# STM32_Minimum_System.net
KiCad netlist of a schematic drawn in EasyEDA Pro
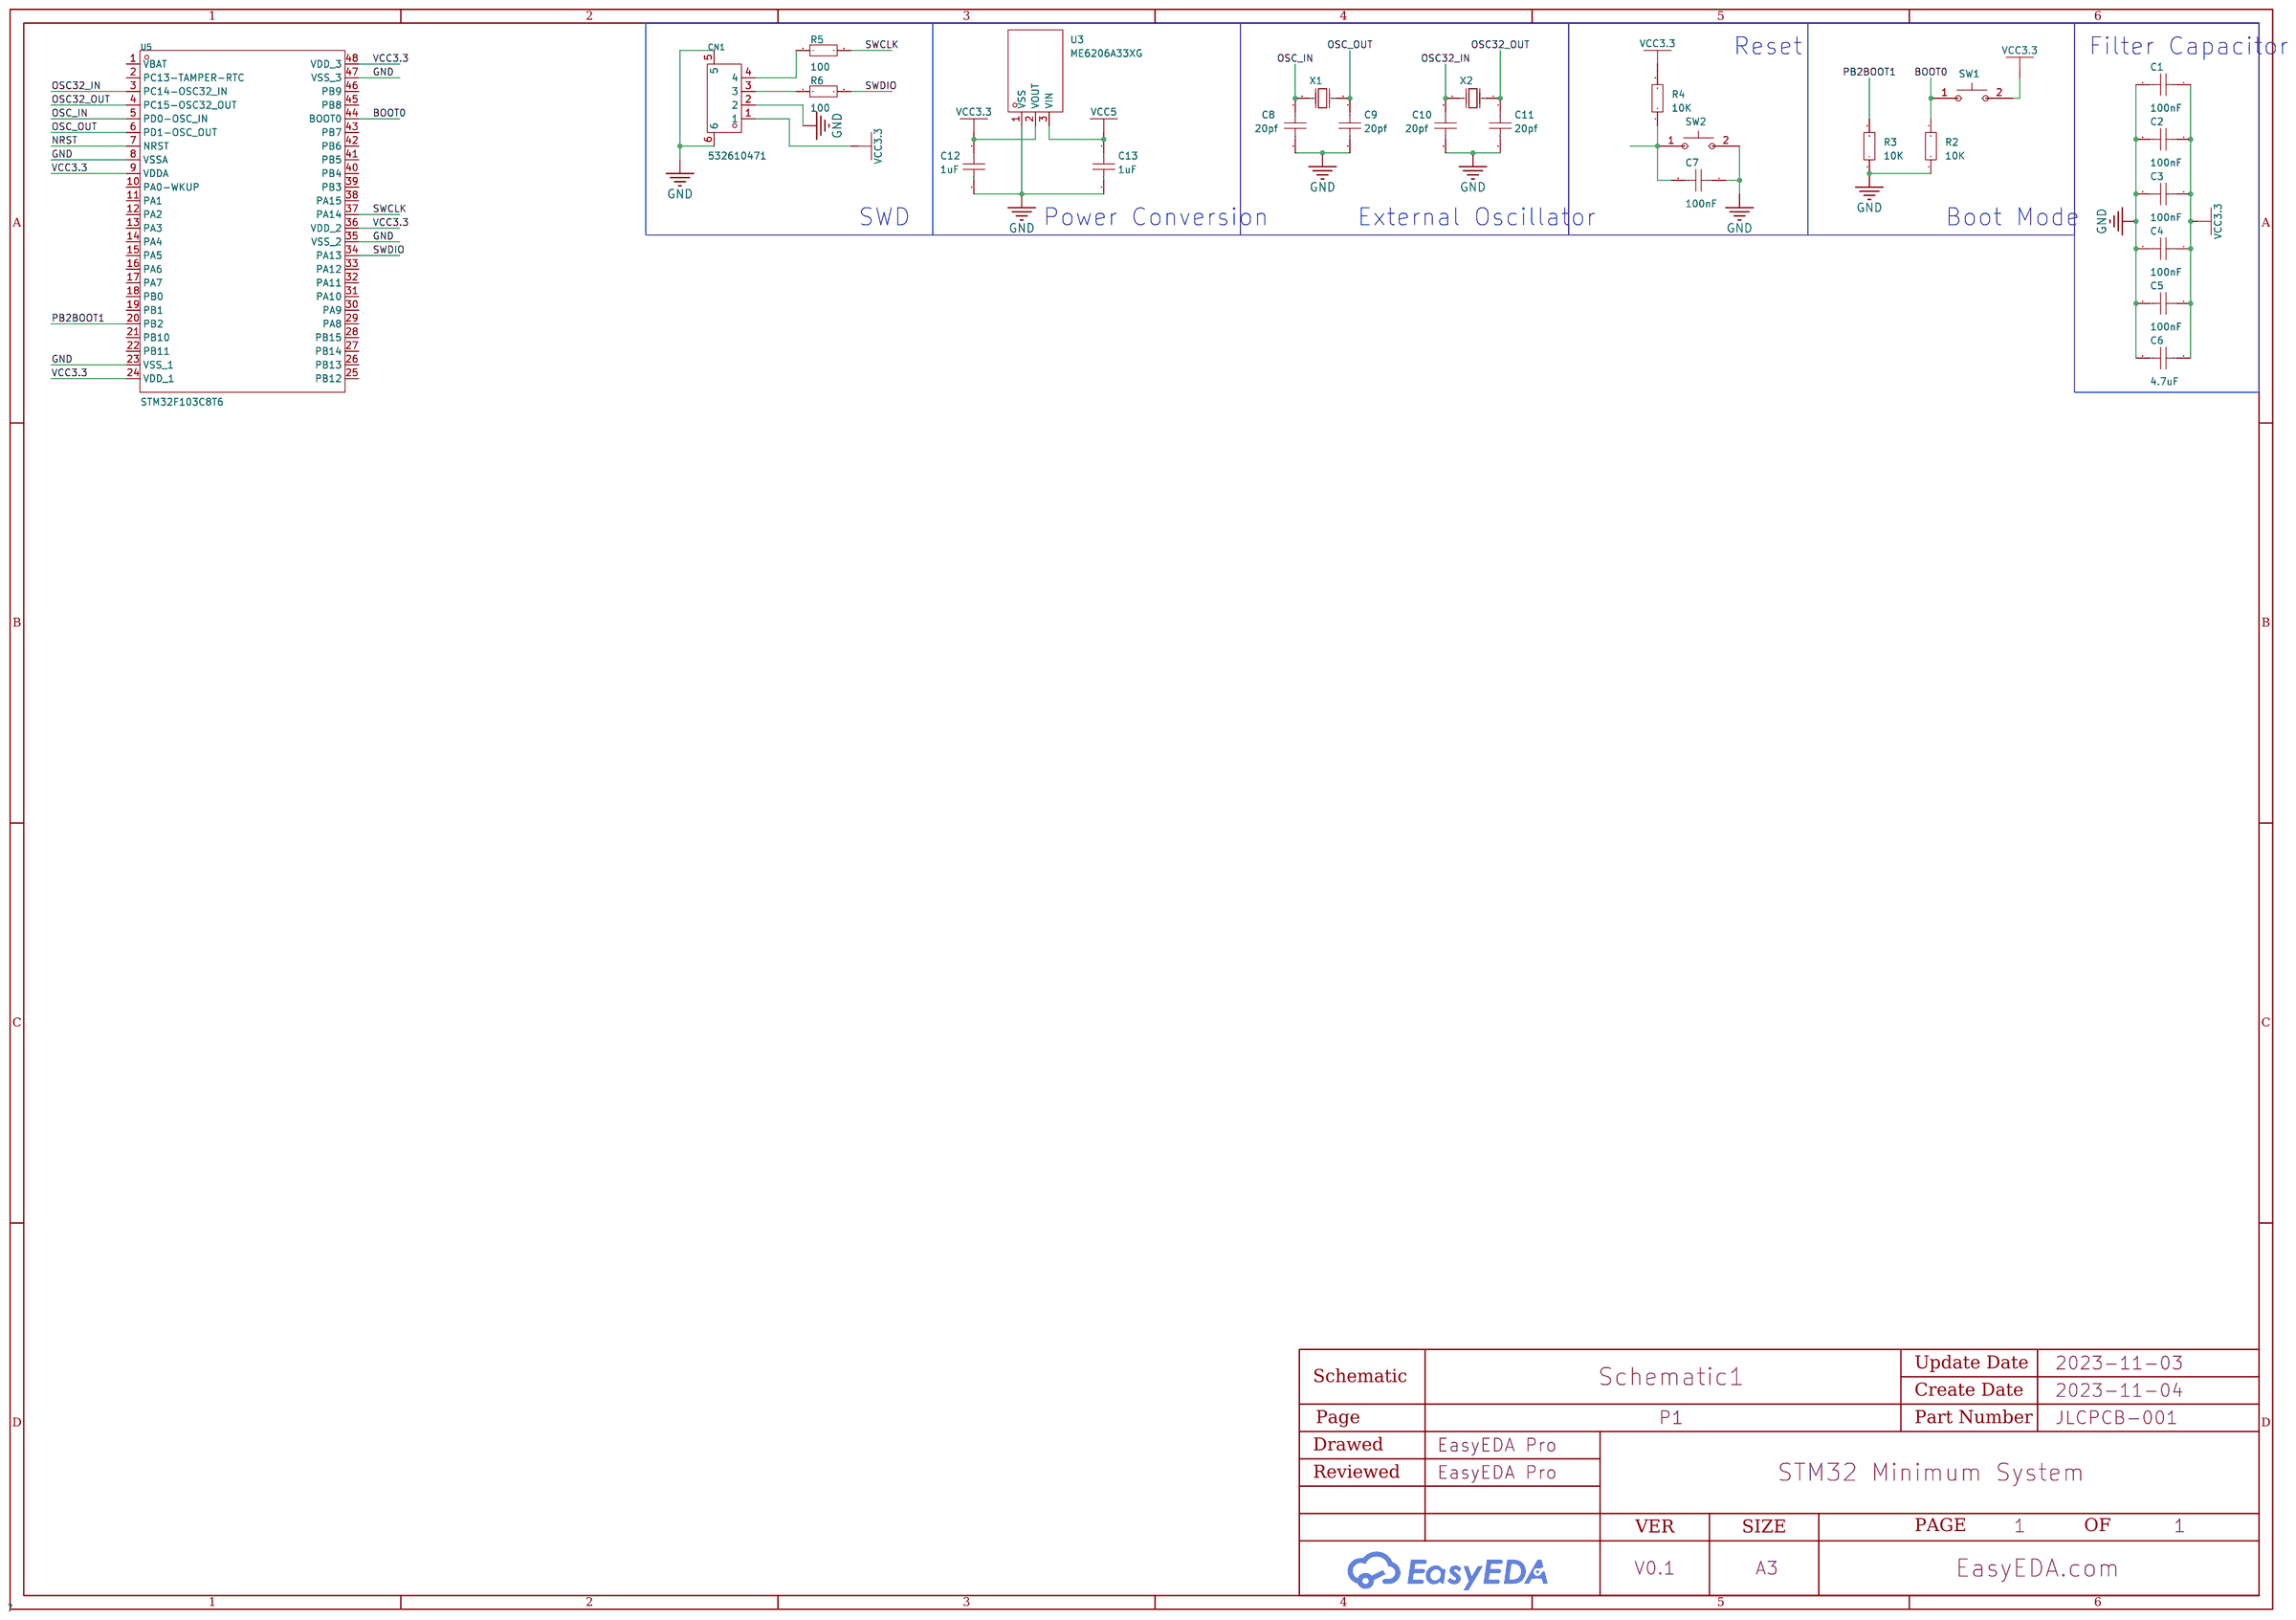
[diagram p0: schematic sheet]

(export (version "E")
  (design (tool "Eeschema 10.0.6"))
  (components
    (comp (ref "C1")
      (value "100nF")
      (footprint "easyedapro:C0603")
      (libsource (lib "easyedapro") (part "CAP"))
    )
    (comp (ref "C2")
      (value "100nF")
      (footprint "easyedapro:C0603")
      (libsource (lib "easyedapro") (part "CAP"))
    )
    (comp (ref "C3")
      (value "100nF")
      (footprint "easyedapro:C0603")
      (libsource (lib "easyedapro") (part "CAP"))
    )
    (comp (ref "C4")
      (value "100nF")
      (footprint "easyedapro:C0603")
      (libsource (lib "easyedapro") (part "CAP"))
    )
    (comp (ref "C5")
      (value "100nF")
      (footprint "easyedapro:C0603")
      (libsource (lib "easyedapro") (part "CAP"))
    )
    (comp (ref "C6")
      (value "4.7uF")
      (footprint "easyedapro:C0603")
      (libsource (lib "easyedapro") (part "CAP"))
    )
    (comp (ref "C7")
      (value "100nF")
      (footprint "easyedapro:C0603")
      (libsource (lib "easyedapro") (part "CAP"))
    )
    (comp (ref "C8")
      (value "20pf")
      (footprint "easyedapro:C0603")
      (libsource (lib "easyedapro") (part "CAP"))
    )
    (comp (ref "C9")
      (value "20pf")
      (footprint "easyedapro:C0603")
      (libsource (lib "easyedapro") (part "CAP"))
    )
    (comp (ref "C10")
      (value "20pf")
      (footprint "easyedapro:C0603")
      (libsource (lib "easyedapro") (part "CAP"))
    )
    (comp (ref "C11")
      (value "20pf")
      (footprint "easyedapro:C0603")
      (libsource (lib "easyedapro") (part "CAP"))
    )
    (comp (ref "C12")
      (value "1uF")
      (footprint "easyedapro:C0603")
      (libsource (lib "easyedapro") (part "CAP"))
    )
    (comp (ref "C13")
      (value "1uF")
      (footprint "easyedapro:C0603")
      (libsource (lib "easyedapro") (part "CAP"))
    )
    (comp (ref "CN1")
      (value "532610471")
      (footprint "easyedapro:CONN-SMD_4P-P1.25_53261-0471")
      (fields (field (name "Manufacturer") "MOLEX"))
      (libsource (lib "easyedapro") (part "53261-0471"))
    )
    (comp (ref "R2") (value "10K") (footprint "easyedapro:R0603") (libsource (lib "easyedapro") (part "Res")))
    (comp (ref "R3") (value "10K") (footprint "easyedapro:R0603") (libsource (lib "easyedapro") (part "Res")))
    (comp (ref "R4") (value "10K") (footprint "easyedapro:R0603") (libsource (lib "easyedapro") (part "Res")))
    (comp (ref "R5") (value "100") (footprint "easyedapro:R0603") (libsource (lib "easyedapro") (part "Res")))
    (comp (ref "R6") (value "100") (footprint "easyedapro:R0603") (libsource (lib "easyedapro") (part "Res")))
    (comp (ref "SW1")
      (value "1TS002C-2300-4300-CT")
      (footprint "easyedapro:SW-SMD_L6.0-W3.5-LS8.0-EH")
      (fields (field (name "Manufacturer") "HYP(鸿源精密)"))
      (libsource (lib "easyedapro") (part "1TS002C-2300-4300"))
    )
    (comp (ref "SW2")
      (value "1TS002C-2300-4300-CT")
      (footprint "easyedapro:SW-SMD_L6.0-W3.5-LS8.0-EH")
      (fields (field (name "Manufacturer") "HYP(鸿源精密)"))
      (libsource (lib "easyedapro") (part "1TS002C-2300-4300"))
    )
    (comp (ref "U3")
      (value "ME6206A33XG")
      (footprint "easyedapro:SOT-23-3_L2.9-W1.6-P1.90-LS2.8-BR")
      (fields (field (name "Manufacturer") "MICRONE(南京微盟)"))
      (libsource (lib "easyedapro") (part "ME6206A33XG"))
    )
    (comp (ref "U5")
      (value "STM32F103C8T6")
      (footprint "easyedapro:LQFP-48_L7.0-W7.0-P0.50-LS9.0-BL")
      (fields (field (name "Manufacturer") "ST(意法半导体)"))
      (libsource (lib "easyedapro") (part "STM32F103C8T6"))
    )
    (comp (ref "X1")
      (value "-")
      (footprint "easyedapro:HC-49US_L11.5-W4.5-P4.88")
      (description "Crystal Type:- Frequency:- Load Capacitance:- Operating Temperature:- Operating Temperature:-")
      (fields (field (name "Manufacturer Part") "9B08000368") (field (name "Manufacturer") "TXC(晶技)"))
      (libsource (lib "easyedapro") (part "9B0808LCSC-AAK2S"))
    )
    (comp (ref "X2")
      (value "-")
      (footprint "easyedapro:OSC-TH_BD2.0-P0.70-D0.3")
      (description "Crystal Type:- Frequency:- Load Capacitance:- Operating Temperature:- Operating Temperature:-")
      (fields (field (name "Manufacturer Part") "DT-26 32.768KHz") (field (name "Manufacturer") "KDS(大真空)"))
      (libsource (lib "easyedapro") (part "DT-26 32.768KHz"))
    )
  )
  (nets
    (net (code "1") (name "/BOOT0") (class "Default")
      (node (ref "R2") (pin "2") (pinfunction "2_2") (pintype "input"))
      (node (ref "SW1") (pin "1") (pinfunction "A_1") (pintype "input"))
      (node (ref "U5") (pin "44") (pinfunction "BOOT0_44") (pintype "input"))
    )
    (net (code "2") (name "/NRST") (class "Default")
      (node (ref "U5") (pin "7") (pinfunction "NRST_7") (pintype "input"))
    )
    (net (code "3") (name "/OSC32_IN") (class "Default")
      (node (ref "C10") (pin "1") (pinfunction "1_1") (pintype "input"))
      (node (ref "U5") (pin "3") (pinfunction "PC14-OSC32_IN_3") (pintype "input"))
      (node (ref "X2") (pin "2") (pinfunction "OSC2_2") (pintype "input"))
    )
    (net (code "4") (name "/OSC32_OUT") (class "Default")
      (node (ref "C11") (pin "1") (pinfunction "1_1") (pintype "input"))
      (node (ref "U5") (pin "4") (pinfunction "PC15-OSC32_OUT_4") (pintype "input"))
      (node (ref "X2") (pin "1") (pinfunction "OSC1_1") (pintype "input"))
    )
    (net (code "5") (name "/OSC_IN") (class "Default")
      (node (ref "C8") (pin "1") (pinfunction "1_1") (pintype "input"))
      (node (ref "U5") (pin "5") (pinfunction "PD0-OSC_IN_5") (pintype "input"))
      (node (ref "X1") (pin "1") (pinfunction "OSC1_1") (pintype "input"))
    )
    (net (code "6") (name "/OSC_OUT") (class "Default")
      (node (ref "C9") (pin "1") (pinfunction "1_1") (pintype "input"))
      (node (ref "U5") (pin "6") (pinfunction "PD1-OSC_OUT_6") (pintype "input"))
      (node (ref "X1") (pin "2") (pinfunction "OSC2_2") (pintype "input"))
    )
    (net (code "7") (name "/PB2BOOT1") (class "Default")
      (node (ref "R3") (pin "2") (pinfunction "2_2") (pintype "input"))
      (node (ref "U5") (pin "20") (pinfunction "PB2_20") (pintype "input"))
    )
    (net (code "8") (name "/SWCLK") (class "Default")
      (node (ref "R5") (pin "2") (pinfunction "2_2") (pintype "input"))
      (node (ref "U5") (pin "37") (pinfunction "PA14_37") (pintype "input"))
    )
    (net (code "9") (name "/SWDIO") (class "Default")
      (node (ref "R6") (pin "2") (pinfunction "2_2") (pintype "input"))
      (node (ref "U5") (pin "34") (pinfunction "PA13_34") (pintype "input"))
    )
    (net (code "10") (name "GND") (class "Default")
      (node (ref "C1") (pin "2") (pinfunction "2_2") (pintype "input"))
      (node (ref "C10") (pin "2") (pinfunction "2_2") (pintype "input"))
      (node (ref "C11") (pin "2") (pinfunction "2_2") (pintype "input"))
      (node (ref "C12") (pin "2") (pinfunction "2_2") (pintype "input"))
      (node (ref "C13") (pin "2") (pinfunction "2_2") (pintype "input"))
      (node (ref "C2") (pin "2") (pinfunction "2_2") (pintype "input"))
      (node (ref "C3") (pin "2") (pinfunction "2_2") (pintype "input"))
      (node (ref "C4") (pin "2") (pinfunction "2_2") (pintype "input"))
      (node (ref "C5") (pin "2") (pinfunction "2_2") (pintype "input"))
      (node (ref "C6") (pin "2") (pinfunction "2_2") (pintype "input"))
      (node (ref "C7") (pin "1") (pinfunction "1_1") (pintype "input"))
      (node (ref "C8") (pin "2") (pinfunction "2_2") (pintype "input"))
      (node (ref "C9") (pin "2") (pinfunction "2_2") (pintype "input"))
      (node (ref "CN1") (pin "2") (pinfunction "2_2") (pintype "input"))
      (node (ref "CN1") (pin "5") (pinfunction "5_5") (pintype "input"))
      (node (ref "CN1") (pin "6") (pinfunction "6_6") (pintype "input"))
      (node (ref "R2") (pin "1") (pinfunction "1_1") (pintype "input"))
      (node (ref "R3") (pin "1") (pinfunction "1_1") (pintype "input"))
      (node (ref "SW2") (pin "2") (pinfunction "B_2") (pintype "input"))
      (node (ref "U3") (pin "1") (pinfunction "VSS_1") (pintype "input"))
      (node (ref "U5") (pin "23") (pinfunction "VSS_1_23") (pintype "input"))
      (node (ref "U5") (pin "35") (pinfunction "VSS_2_35") (pintype "input"))
      (node (ref "U5") (pin "47") (pinfunction "VSS_3_47") (pintype "input"))
      (node (ref "U5") (pin "8") (pinfunction "VSSA_8") (pintype "input"))
    )
    (net (code "11") (name "Net-(CN1-Pad3)") (class "Default")
      (node (ref "CN1") (pin "3") (pinfunction "3_3") (pintype "input"))
      (node (ref "R6") (pin "1") (pinfunction "1_1") (pintype "input"))
    )
    (net (code "12") (name "Net-(CN1-Pad4)") (class "Default")
      (node (ref "CN1") (pin "4") (pinfunction "4_4") (pintype "input"))
      (node (ref "R5") (pin "1") (pinfunction "1_1") (pintype "input"))
    )
    (net (code "13") (name "Net-(SW2-A)") (class "Default")
      (node (ref "C7") (pin "2") (pinfunction "2_2") (pintype "input"))
      (node (ref "R4") (pin "1") (pinfunction "1_1") (pintype "input"))
      (node (ref "SW2") (pin "1") (pinfunction "A_1") (pintype "input"))
    )
    (net (code "14") (name "VCC3.3") (class "Default")
      (node (ref "C1") (pin "1") (pinfunction "1_1") (pintype "input"))
      (node (ref "C12") (pin "1") (pinfunction "1_1") (pintype "input"))
      (node (ref "C2") (pin "1") (pinfunction "1_1") (pintype "input"))
      (node (ref "C3") (pin "1") (pinfunction "1_1") (pintype "input"))
      (node (ref "C4") (pin "1") (pinfunction "1_1") (pintype "input"))
      (node (ref "C5") (pin "1") (pinfunction "1_1") (pintype "input"))
      (node (ref "C6") (pin "1") (pinfunction "1_1") (pintype "input"))
      (node (ref "CN1") (pin "1") (pinfunction "1_1") (pintype "input"))
      (node (ref "R4") (pin "2") (pinfunction "2_2") (pintype "input"))
      (node (ref "SW1") (pin "2") (pinfunction "B_2") (pintype "input"))
      (node (ref "U3") (pin "2") (pinfunction "VOUT_2") (pintype "input"))
      (node (ref "U5") (pin "24") (pinfunction "VDD_1_24") (pintype "input"))
      (node (ref "U5") (pin "36") (pinfunction "VDD_2_36") (pintype "input"))
      (node (ref "U5") (pin "48") (pinfunction "VDD_3_48") (pintype "input"))
      (node (ref "U5") (pin "9") (pinfunction "VDDA_9") (pintype "input"))
    )
    (net (code "15") (name "VCC5") (class "Default")
      (node (ref "C13") (pin "1") (pinfunction "1_1") (pintype "input"))
      (node (ref "U3") (pin "3") (pinfunction "VIN_3") (pintype "input"))
    )
    (net (code "16") (name "unconnected-(U5-PA0-WKUP-Pad10)") (class "Default")
      (node (ref "U5") (pin "10") (pinfunction "PA0-WKUP_10") (pintype "input"))
    )
    (net (code "17") (name "unconnected-(U5-PA1-Pad11)") (class "Default")
      (node (ref "U5") (pin "11") (pinfunction "PA1_11") (pintype "input"))
    )
    (net (code "18") (name "unconnected-(U5-PA2-Pad12)") (class "Default")
      (node (ref "U5") (pin "12") (pinfunction "PA2_12") (pintype "input"))
    )
    (net (code "19") (name "unconnected-(U5-PA3-Pad13)") (class "Default")
      (node (ref "U5") (pin "13") (pinfunction "PA3_13") (pintype "input"))
    )
    (net (code "20") (name "unconnected-(U5-PA4-Pad14)") (class "Default")
      (node (ref "U5") (pin "14") (pinfunction "PA4_14") (pintype "input"))
    )
    (net (code "21") (name "unconnected-(U5-PA5-Pad15)") (class "Default")
      (node (ref "U5") (pin "15") (pinfunction "PA5_15") (pintype "input"))
    )
    (net (code "22") (name "unconnected-(U5-PA6-Pad16)") (class "Default")
      (node (ref "U5") (pin "16") (pinfunction "PA6_16") (pintype "input"))
    )
    (net (code "23") (name "unconnected-(U5-PA7-Pad17)") (class "Default")
      (node (ref "U5") (pin "17") (pinfunction "PA7_17") (pintype "input"))
    )
    (net (code "24") (name "unconnected-(U5-PA8-Pad29)") (class "Default")
      (node (ref "U5") (pin "29") (pinfunction "PA8_29") (pintype "input"))
    )
    (net (code "25") (name "unconnected-(U5-PA9-Pad30)") (class "Default")
      (node (ref "U5") (pin "30") (pinfunction "PA9_30") (pintype "input"))
    )
    (net (code "26") (name "unconnected-(U5-PA10-Pad31)") (class "Default")
      (node (ref "U5") (pin "31") (pinfunction "PA10_31") (pintype "input"))
    )
    (net (code "27") (name "unconnected-(U5-PA11-Pad32)") (class "Default")
      (node (ref "U5") (pin "32") (pinfunction "PA11_32") (pintype "input"))
    )
    (net (code "28") (name "unconnected-(U5-PA12-Pad33)") (class "Default")
      (node (ref "U5") (pin "33") (pinfunction "PA12_33") (pintype "input"))
    )
    (net (code "29") (name "unconnected-(U5-PA15-Pad38)") (class "Default")
      (node (ref "U5") (pin "38") (pinfunction "PA15_38") (pintype "input"))
    )
    (net (code "30") (name "unconnected-(U5-PB0-Pad18)") (class "Default")
      (node (ref "U5") (pin "18") (pinfunction "PB0_18") (pintype "input"))
    )
    (net (code "31") (name "unconnected-(U5-PB1-Pad19)") (class "Default")
      (node (ref "U5") (pin "19") (pinfunction "PB1_19") (pintype "input"))
    )
    (net (code "32") (name "unconnected-(U5-PB3-Pad39)") (class "Default")
      (node (ref "U5") (pin "39") (pinfunction "PB3_39") (pintype "input"))
    )
    (net (code "33") (name "unconnected-(U5-PB4-Pad40)") (class "Default")
      (node (ref "U5") (pin "40") (pinfunction "PB4_40") (pintype "input"))
    )
    (net (code "34") (name "unconnected-(U5-PB5-Pad41)") (class "Default")
      (node (ref "U5") (pin "41") (pinfunction "PB5_41") (pintype "input"))
    )
    (net (code "35") (name "unconnected-(U5-PB6-Pad42)") (class "Default")
      (node (ref "U5") (pin "42") (pinfunction "PB6_42") (pintype "input"))
    )
    (net (code "36") (name "unconnected-(U5-PB7-Pad43)") (class "Default")
      (node (ref "U5") (pin "43") (pinfunction "PB7_43") (pintype "input"))
    )
    (net (code "37") (name "unconnected-(U5-PB8-Pad45)") (class "Default")
      (node (ref "U5") (pin "45") (pinfunction "PB8_45") (pintype "input"))
    )
    (net (code "38") (name "unconnected-(U5-PB9-Pad46)") (class "Default")
      (node (ref "U5") (pin "46") (pinfunction "PB9_46") (pintype "input"))
    )
    (net (code "39") (name "unconnected-(U5-PB10-Pad21)") (class "Default")
      (node (ref "U5") (pin "21") (pinfunction "PB10_21") (pintype "input"))
    )
    (net (code "40") (name "unconnected-(U5-PB11-Pad22)") (class "Default")
      (node (ref "U5") (pin "22") (pinfunction "PB11_22") (pintype "input"))
    )
    (net (code "41") (name "unconnected-(U5-PB12-Pad25)") (class "Default")
      (node (ref "U5") (pin "25") (pinfunction "PB12_25") (pintype "input"))
    )
    (net (code "42") (name "unconnected-(U5-PB13-Pad26)") (class "Default")
      (node (ref "U5") (pin "26") (pinfunction "PB13_26") (pintype "input"))
    )
    (net (code "43") (name "unconnected-(U5-PB14-Pad27)") (class "Default")
      (node (ref "U5") (pin "27") (pinfunction "PB14_27") (pintype "input"))
    )
    (net (code "44") (name "unconnected-(U5-PB15-Pad28)") (class "Default")
      (node (ref "U5") (pin "28") (pinfunction "PB15_28") (pintype "input"))
    )
    (net (code "45") (name "unconnected-(U5-PC13-TAMPER-RTC-Pad2)") (class "Default")
      (node (ref "U5") (pin "2") (pinfunction "PC13-TAMPER-RTC_2") (pintype "input"))
    )
    (net (code "46") (name "unconnected-(U5-VBAT-Pad1)") (class "Default")
      (node (ref "U5") (pin "1") (pinfunction "VBAT_1") (pintype "input"))
    )
  )
)
